# SCH.net
KiCad netlist of a schematic drawn in EasyEDA
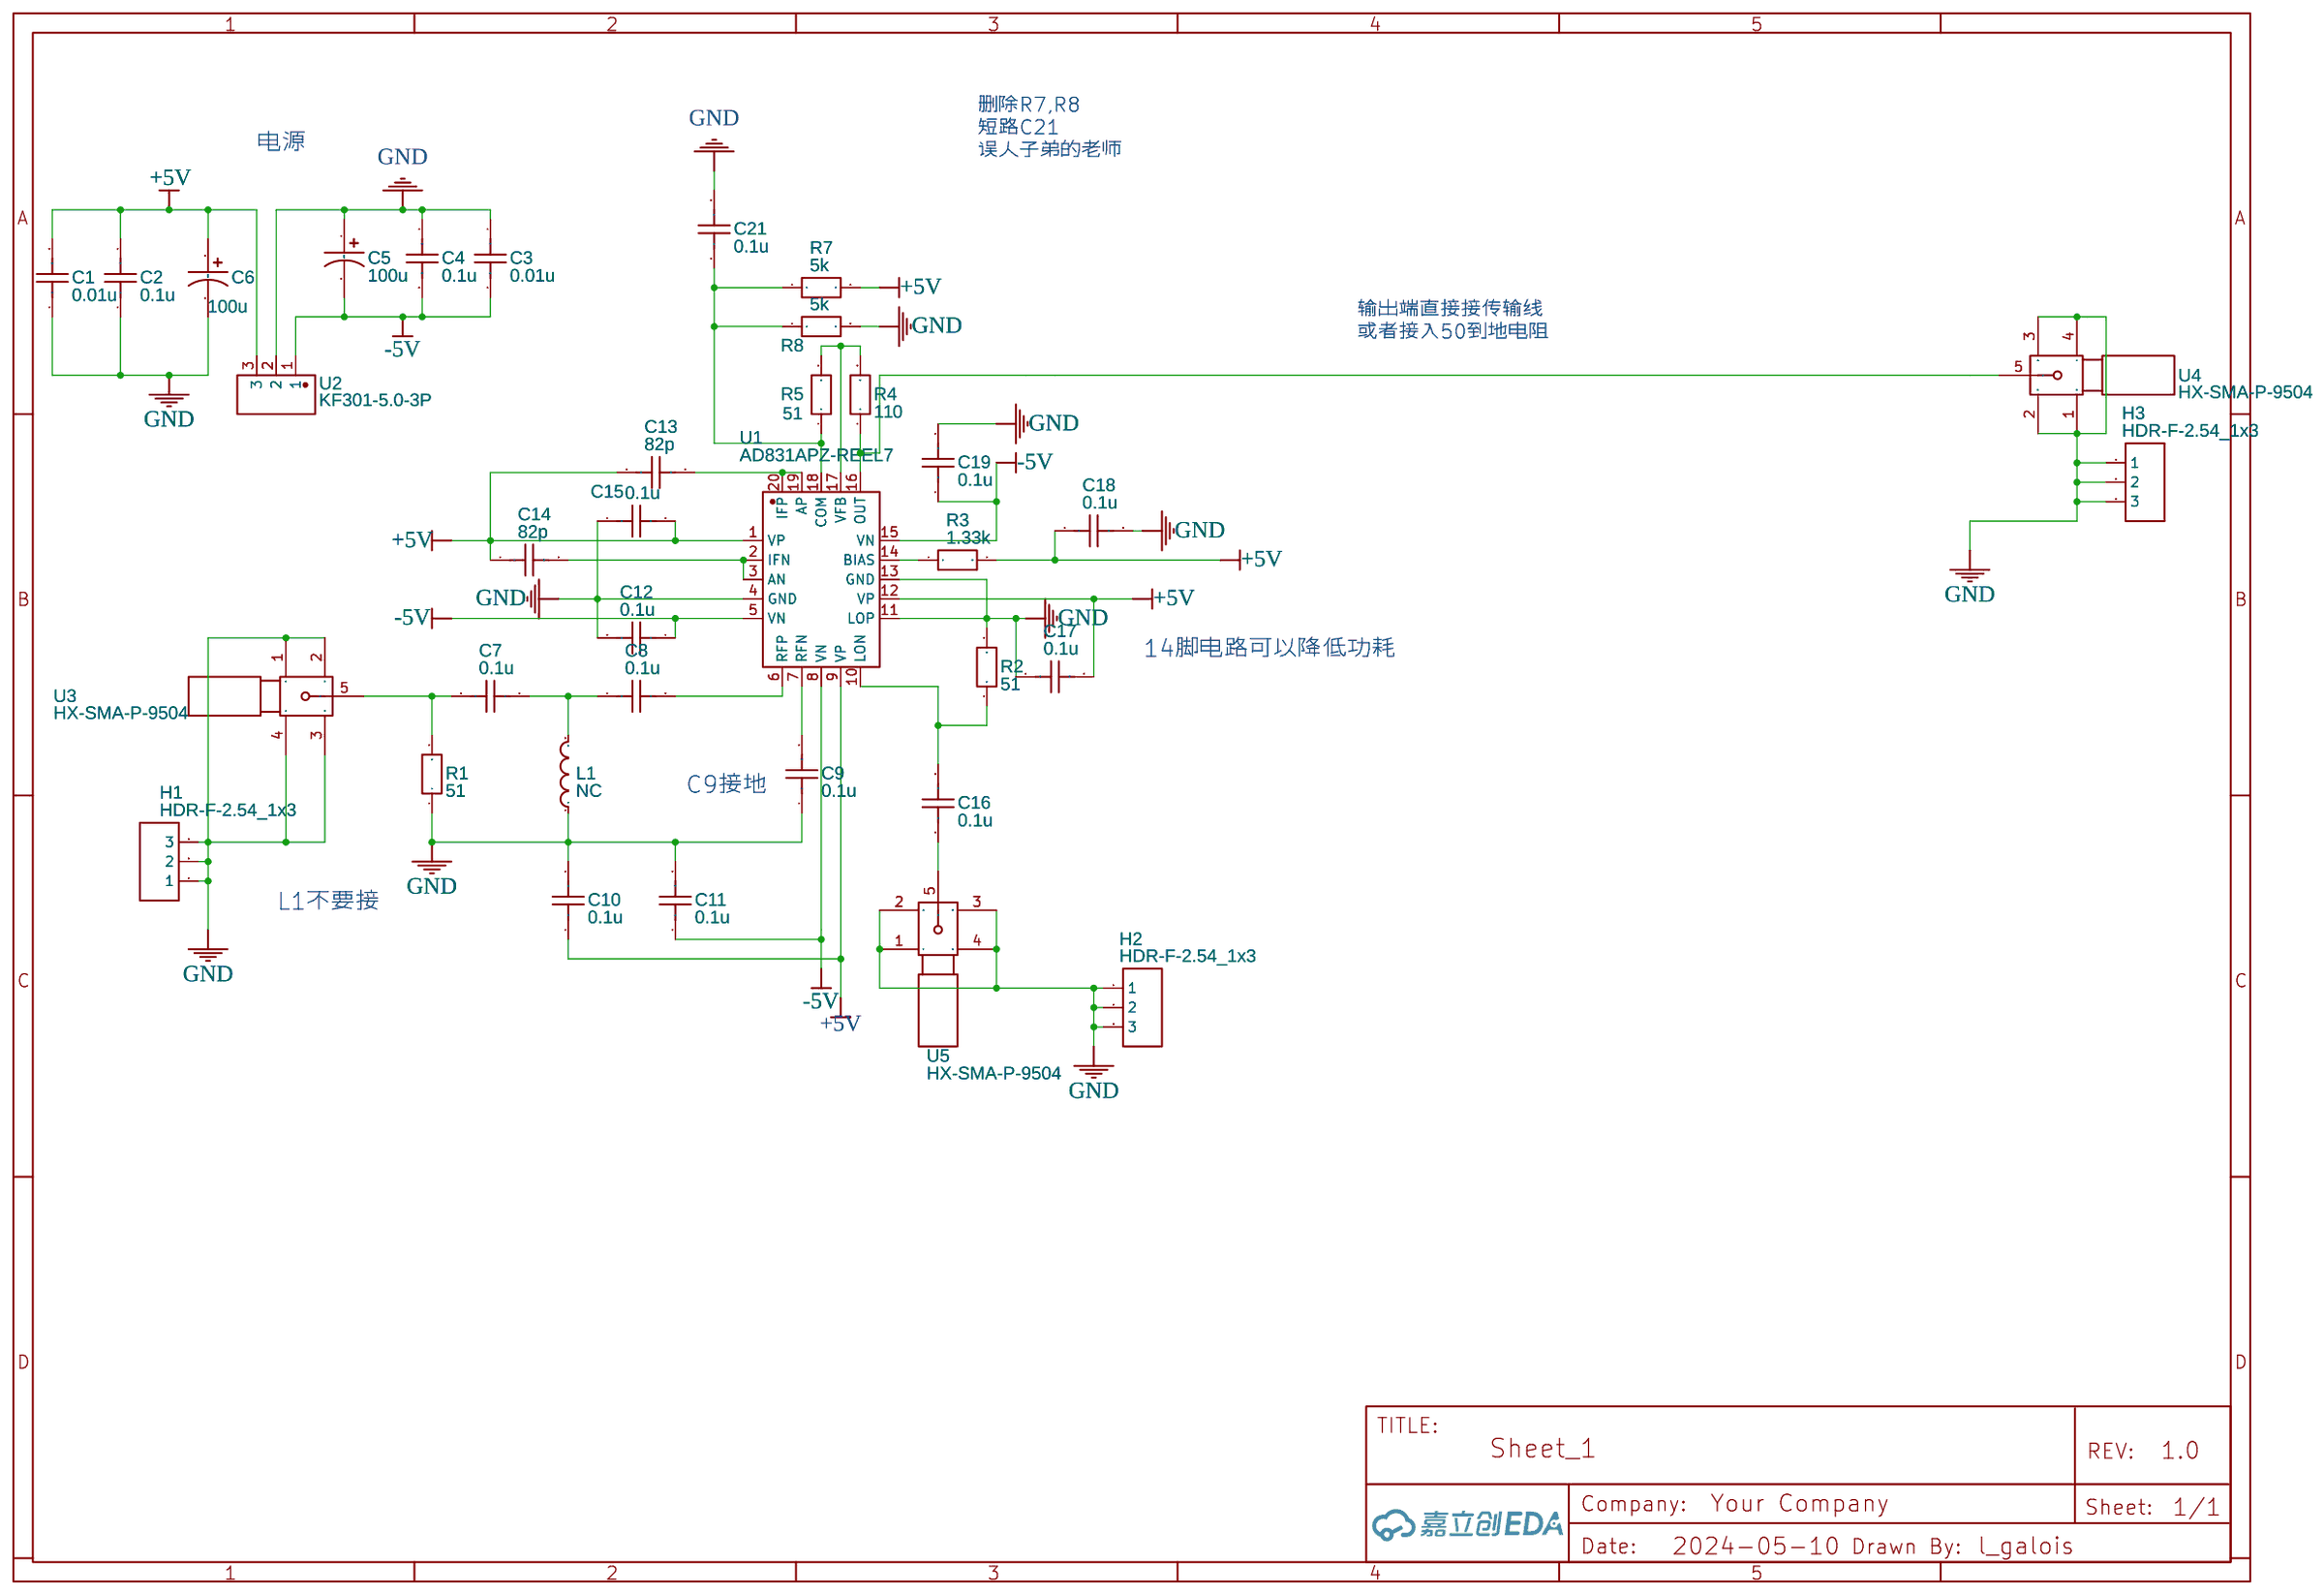
[diagram p0: schematic sheet]

(export (version "E")
  (design (tool "Eeschema 10.0.6"))
  (components
    (comp (ref "C1") (value "0.01u") (libsource (lib "") (part "C_0805_US_1")))
    (comp (ref "C2") (value "0.1u") (libsource (lib "") (part "C_0805_US_1")))
    (comp (ref "C3") (value "0.01u") (libsource (lib "") (part "C_0805_US_2")))
    (comp (ref "C4") (value "0.1u") (libsource (lib "") (part "C_0805_US_2")))
    (comp (ref "C5") (value "100u") (libsource (lib "") (part "C_Tan_SMD_A_US")))
    (comp (ref "C6") (value "100u") (libsource (lib "") (part "CE_SMD_D8.0×H10.5_US")))
    (comp (ref "C7") (value "0.1u") (libsource (lib "") (part "C_0805_US")))
    (comp (ref "C8") (value "0.1u") (libsource (lib "") (part "C_0805_US")))
    (comp (ref "C9") (value "0.1u") (libsource (lib "") (part "C_0805_US_1")))
    (comp (ref "C10") (value "0.1u") (libsource (lib "") (part "C_0805_US_1")))
    (comp (ref "C11") (value "0.1u") (libsource (lib "") (part "C_0805_US_1")))
    (comp (ref "C12") (value "0.1u") (libsource (lib "") (part "C_0805_US_3")))
    (comp (ref "C13") (value "82p") (libsource (lib "") (part "C_0805_US")))
    (comp (ref "C14") (value "82p") (libsource (lib "") (part "C_0805_US")))
    (comp (ref "C15") (value "0.1u") (libsource (lib "") (part "C_0805_US")))
    (comp (ref "C16") (value "0.1u") (libsource (lib "") (part "C_0805_US_1")))
    (comp (ref "C17") (value "0.1u") (libsource (lib "") (part "C_0805_US")))
    (comp (ref "C18") (value "0.1u") (libsource (lib "") (part "C_0805_US")))
    (comp (ref "C19") (value "0.1u") (libsource (lib "") (part "C_0805_US_1")))
    (comp (ref "C21") (value "0.1u") (libsource (lib "") (part "C_0805_US_1")))
    (comp (ref "H1") (value "HDR-F-2.54_1x3") (libsource (lib "") (part "HDR-F-2.54_1x3_1")))
    (comp (ref "H2") (value "HDR-F-2.54_1x3") (libsource (lib "") (part "HDR-F-2.54_1x3")))
    (comp (ref "H3") (value "HDR-F-2.54_1x3") (libsource (lib "") (part "HDR-F-2.54_1x3")))
    (comp (ref "L1") (value "NC") (libsource (lib "") (part "L0805_US")))
    (comp (ref "R1") (value "51") (libsource (lib "") (part "R_0805_EU")))
    (comp (ref "R2") (value "51") (libsource (lib "") (part "R_0805_EU")))
    (comp (ref "R3") (value "1.33k") (libsource (lib "") (part "R_0805_EU_1")))
    (comp (ref "R4") (value "110") (libsource (lib "") (part "R_0805_EU")))
    (comp (ref "R5") (value "51") (libsource (lib "") (part "R_0805_EU")))
    (comp (ref "R7") (value "5k") (libsource (lib "") (part "R_0805_EU_1")))
    (comp (ref "R8") (value "5k") (libsource (lib "") (part "R_0805_EU_1")))
    (comp (ref "U1")
      (value "AD831APZ-REEL7")
      (fields (field (name "Manufacturer") "ADI(亚德诺)"))
      (libsource (lib "") (part "AD831APZ-REEL7"))
    )
    (comp (ref "U2")
      (value "KF301-5.0-3P")
      (fields (field (name "Manufacturer") "KEFA(科发)"))
      (libsource (lib "") (part "KF301-5.0-3P"))
    )
    (comp (ref "U3")
      (value "HX-SMA-P-9504")
      (fields (field (name "Manufacturer") "环协"))
      (libsource (lib "") (part "HX-SMA-P-9504_2"))
    )
    (comp (ref "U4")
      (value "HX-SMA-P-9504")
      (fields (field (name "Manufacturer") "环协"))
      (libsource (lib "") (part "HX-SMA-P-9504_1"))
    )
    (comp (ref "U5")
      (value "HX-SMA-P-9504")
      (fields (field (name "Manufacturer") "环协"))
      (libsource (lib "") (part "HX-SMA-P-9504"))
    )
  )
  (nets
    (net (code "1") (name "+5V") (class "Default")
      (node (ref "C1") (pin "2") (pinfunction "2_2") (pintype "unspecified"))
      (node (ref "C10") (pin "1") (pinfunction "1_1") (pintype "unspecified"))
      (node (ref "C13") (pin "1") (pinfunction "1_1") (pintype "unspecified"))
      (node (ref "C14") (pin "1") (pinfunction "1_1") (pintype "unspecified"))
      (node (ref "C15") (pin "2") (pinfunction "2_2") (pintype "unspecified"))
      (node (ref "C17") (pin "2") (pinfunction "2_2") (pintype "unspecified"))
      (node (ref "C18") (pin "1") (pinfunction "1_1") (pintype "unspecified"))
      (node (ref "C2") (pin "2") (pinfunction "2_2") (pintype "unspecified"))
      (node (ref "C6") (pin "1") (pinfunction "1_1") (pintype "unspecified"))
      (node (ref "R3") (pin "2") (pinfunction "2_2") (pintype "unspecified"))
      (node (ref "R7") (pin "2") (pinfunction "2_2") (pintype "unspecified"))
      (node (ref "U1") (pin "1") (pinfunction "VP_1") (pintype "unspecified"))
      (node (ref "U1") (pin "12") (pinfunction "VP_12") (pintype "unspecified"))
      (node (ref "U1") (pin "9") (pinfunction "VP_9") (pintype "unspecified"))
      (node (ref "U2") (pin "3") (pinfunction "3_3") (pintype "unspecified"))
    )
    (net (code "2") (name "-5V") (class "Default")
      (node (ref "C11") (pin "1") (pinfunction "1_1") (pintype "unspecified"))
      (node (ref "C12") (pin "1") (pinfunction "1_1") (pintype "unspecified"))
      (node (ref "C19") (pin "1") (pinfunction "1_1") (pintype "unspecified"))
      (node (ref "C3") (pin "2") (pinfunction "2_2") (pintype "unspecified"))
      (node (ref "C4") (pin "2") (pinfunction "2_2") (pintype "unspecified"))
      (node (ref "C5") (pin "2") (pinfunction "2_2") (pintype "unspecified"))
      (node (ref "U1") (pin "15") (pinfunction "VN_15") (pintype "unspecified"))
      (node (ref "U1") (pin "5") (pinfunction "VN_5") (pintype "unspecified"))
      (node (ref "U1") (pin "8") (pinfunction "VN_8") (pintype "unspecified"))
      (node (ref "U2") (pin "1") (pinfunction "1_1") (pintype "unspecified"))
    )
    (net (code "3") (name "GND") (class "Default")
      (node (ref "C1") (pin "1") (pinfunction "1_1") (pintype "unspecified"))
      (node (ref "C10") (pin "2") (pinfunction "2_2") (pintype "unspecified"))
      (node (ref "C11") (pin "2") (pinfunction "2_2") (pintype "unspecified"))
      (node (ref "C12") (pin "2") (pinfunction "2_2") (pintype "unspecified"))
      (node (ref "C15") (pin "1") (pinfunction "1_1") (pintype "unspecified"))
      (node (ref "C17") (pin "1") (pinfunction "1_1") (pintype "unspecified"))
      (node (ref "C18") (pin "2") (pinfunction "2_2") (pintype "unspecified"))
      (node (ref "C19") (pin "2") (pinfunction "2_2") (pintype "unspecified"))
      (node (ref "C2") (pin "1") (pinfunction "1_1") (pintype "unspecified"))
      (node (ref "C21") (pin "2") (pinfunction "2_2") (pintype "unspecified"))
      (node (ref "C3") (pin "1") (pinfunction "1_1") (pintype "unspecified"))
      (node (ref "C4") (pin "1") (pinfunction "1_1") (pintype "unspecified"))
      (node (ref "C5") (pin "1") (pinfunction "1_1") (pintype "unspecified"))
      (node (ref "C6") (pin "2") (pinfunction "2_2") (pintype "unspecified"))
      (node (ref "C9") (pin "1") (pinfunction "1_1") (pintype "unspecified"))
      (node (ref "H1") (pin "1") (pinfunction "1_1") (pintype "input"))
      (node (ref "H1") (pin "2") (pinfunction "2_2") (pintype "input"))
      (node (ref "H1") (pin "3") (pinfunction "3_3") (pintype "input"))
      (node (ref "H2") (pin "1") (pinfunction "1_1") (pintype "input"))
      (node (ref "H2") (pin "2") (pinfunction "2_2") (pintype "input"))
      (node (ref "H2") (pin "3") (pinfunction "3_3") (pintype "input"))
      (node (ref "H3") (pin "1") (pinfunction "1_1") (pintype "input"))
      (node (ref "H3") (pin "2") (pinfunction "2_2") (pintype "input"))
      (node (ref "H3") (pin "3") (pinfunction "3_3") (pintype "input"))
      (node (ref "L1") (pin "1") (pinfunction "1_1") (pintype "unspecified"))
      (node (ref "R1") (pin "1") (pinfunction "1_1") (pintype "unspecified"))
      (node (ref "R2") (pin "2") (pinfunction "2_2") (pintype "unspecified"))
      (node (ref "R8") (pin "2") (pinfunction "2_2") (pintype "unspecified"))
      (node (ref "U1") (pin "11") (pinfunction "LOP_11") (pintype "unspecified"))
      (node (ref "U1") (pin "13") (pinfunction "GND_13") (pintype "unspecified"))
      (node (ref "U1") (pin "4") (pinfunction "GND_4") (pintype "unspecified"))
      (node (ref "U2") (pin "2") (pinfunction "2_2") (pintype "unspecified"))
      (node (ref "U3") (pin "1") (pinfunction "1_1") (pintype "unspecified"))
      (node (ref "U3") (pin "2") (pinfunction "2_2") (pintype "unspecified"))
      (node (ref "U3") (pin "3") (pinfunction "3_3") (pintype "unspecified"))
      (node (ref "U3") (pin "4") (pinfunction "4_4") (pintype "unspecified"))
      (node (ref "U4") (pin "1") (pinfunction "1_1") (pintype "unspecified"))
      (node (ref "U4") (pin "2") (pinfunction "2_2") (pintype "unspecified"))
      (node (ref "U4") (pin "3") (pinfunction "3_3") (pintype "unspecified"))
      (node (ref "U4") (pin "4") (pinfunction "4_4") (pintype "unspecified"))
      (node (ref "U5") (pin "1") (pinfunction "1_1") (pintype "unspecified"))
      (node (ref "U5") (pin "2") (pinfunction "2_2") (pintype "unspecified"))
      (node (ref "U5") (pin "3") (pinfunction "3_3") (pintype "unspecified"))
      (node (ref "U5") (pin "4") (pinfunction "4_4") (pintype "unspecified"))
    )
    (net (code "4") (name "Net-(C7-Pad1)") (class "Default")
      (node (ref "C7") (pin "1") (pinfunction "1_1") (pintype "unspecified"))
      (node (ref "R1") (pin "2") (pinfunction "2_2") (pintype "unspecified"))
      (node (ref "U3") (pin "5") (pinfunction "5_5") (pintype "unspecified"))
    )
    (net (code "5") (name "Net-(C7-Pad2)") (class "Default")
      (node (ref "C7") (pin "2") (pinfunction "2_2") (pintype "unspecified"))
      (node (ref "C8") (pin "1") (pinfunction "1_1") (pintype "unspecified"))
      (node (ref "L1") (pin "2") (pinfunction "2_2") (pintype "unspecified"))
    )
    (net (code "6") (name "Net-(C16-Pad1)") (class "Default")
      (node (ref "C16") (pin "1") (pinfunction "1_1") (pintype "unspecified"))
      (node (ref "U5") (pin "5") (pinfunction "5_5") (pintype "unspecified"))
    )
    (net (code "7") (name "Net-(U1-AN)") (class "Default")
      (node (ref "C14") (pin "2") (pinfunction "2_2") (pintype "unspecified"))
      (node (ref "U1") (pin "2") (pinfunction "IFN_2") (pintype "unspecified"))
      (node (ref "U1") (pin "3") (pinfunction "AN_3") (pintype "unspecified"))
    )
    (net (code "8") (name "Net-(U1-AP)") (class "Default")
      (node (ref "C13") (pin "2") (pinfunction "2_2") (pintype "unspecified"))
      (node (ref "U1") (pin "19") (pinfunction "AP_19") (pintype "unspecified"))
      (node (ref "U1") (pin "20") (pinfunction "IFP_20") (pintype "unspecified"))
    )
    (net (code "9") (name "Net-(U1-BIAS)") (class "Default")
      (node (ref "R3") (pin "1") (pinfunction "1_1") (pintype "unspecified"))
      (node (ref "U1") (pin "14") (pinfunction "BIAS_14") (pintype "unspecified"))
    )
    (net (code "10") (name "Net-(U1-COM)") (class "Default")
      (node (ref "C21") (pin "1") (pinfunction "1_1") (pintype "unspecified"))
      (node (ref "R5") (pin "1") (pinfunction "1_1") (pintype "unspecified"))
      (node (ref "R7") (pin "1") (pinfunction "1_1") (pintype "unspecified"))
      (node (ref "R8") (pin "1") (pinfunction "1_1") (pintype "unspecified"))
      (node (ref "U1") (pin "18") (pinfunction "COM_18") (pintype "unspecified"))
    )
    (net (code "11") (name "Net-(U1-LON)") (class "Default")
      (node (ref "C16") (pin "2") (pinfunction "2_2") (pintype "unspecified"))
      (node (ref "R2") (pin "1") (pinfunction "1_1") (pintype "unspecified"))
      (node (ref "U1") (pin "10") (pinfunction "LON_10") (pintype "unspecified"))
    )
    (net (code "12") (name "Net-(U1-OUT)") (class "Default")
      (node (ref "R4") (pin "1") (pinfunction "1_1") (pintype "unspecified"))
      (node (ref "U1") (pin "16") (pinfunction "OUT_16") (pintype "unspecified"))
      (node (ref "U4") (pin "5") (pinfunction "5_5") (pintype "unspecified"))
    )
    (net (code "13") (name "Net-(U1-RFN)") (class "Default")
      (node (ref "C9") (pin "2") (pinfunction "2_2") (pintype "unspecified"))
      (node (ref "U1") (pin "7") (pinfunction "RFN_7") (pintype "unspecified"))
    )
    (net (code "14") (name "Net-(U1-RFP)") (class "Default")
      (node (ref "C8") (pin "2") (pinfunction "2_2") (pintype "unspecified"))
      (node (ref "U1") (pin "6") (pinfunction "RFP_6") (pintype "unspecified"))
    )
    (net (code "15") (name "Net-(U1-VFB)") (class "Default")
      (node (ref "R4") (pin "2") (pinfunction "2_2") (pintype "unspecified"))
      (node (ref "R5") (pin "2") (pinfunction "2_2") (pintype "unspecified"))
      (node (ref "U1") (pin "17") (pinfunction "VFB_17") (pintype "unspecified"))
    )
  )
)
